# NRF24-zero-SHIM.net
KiCad netlist of a schematic drawn in EAGLE
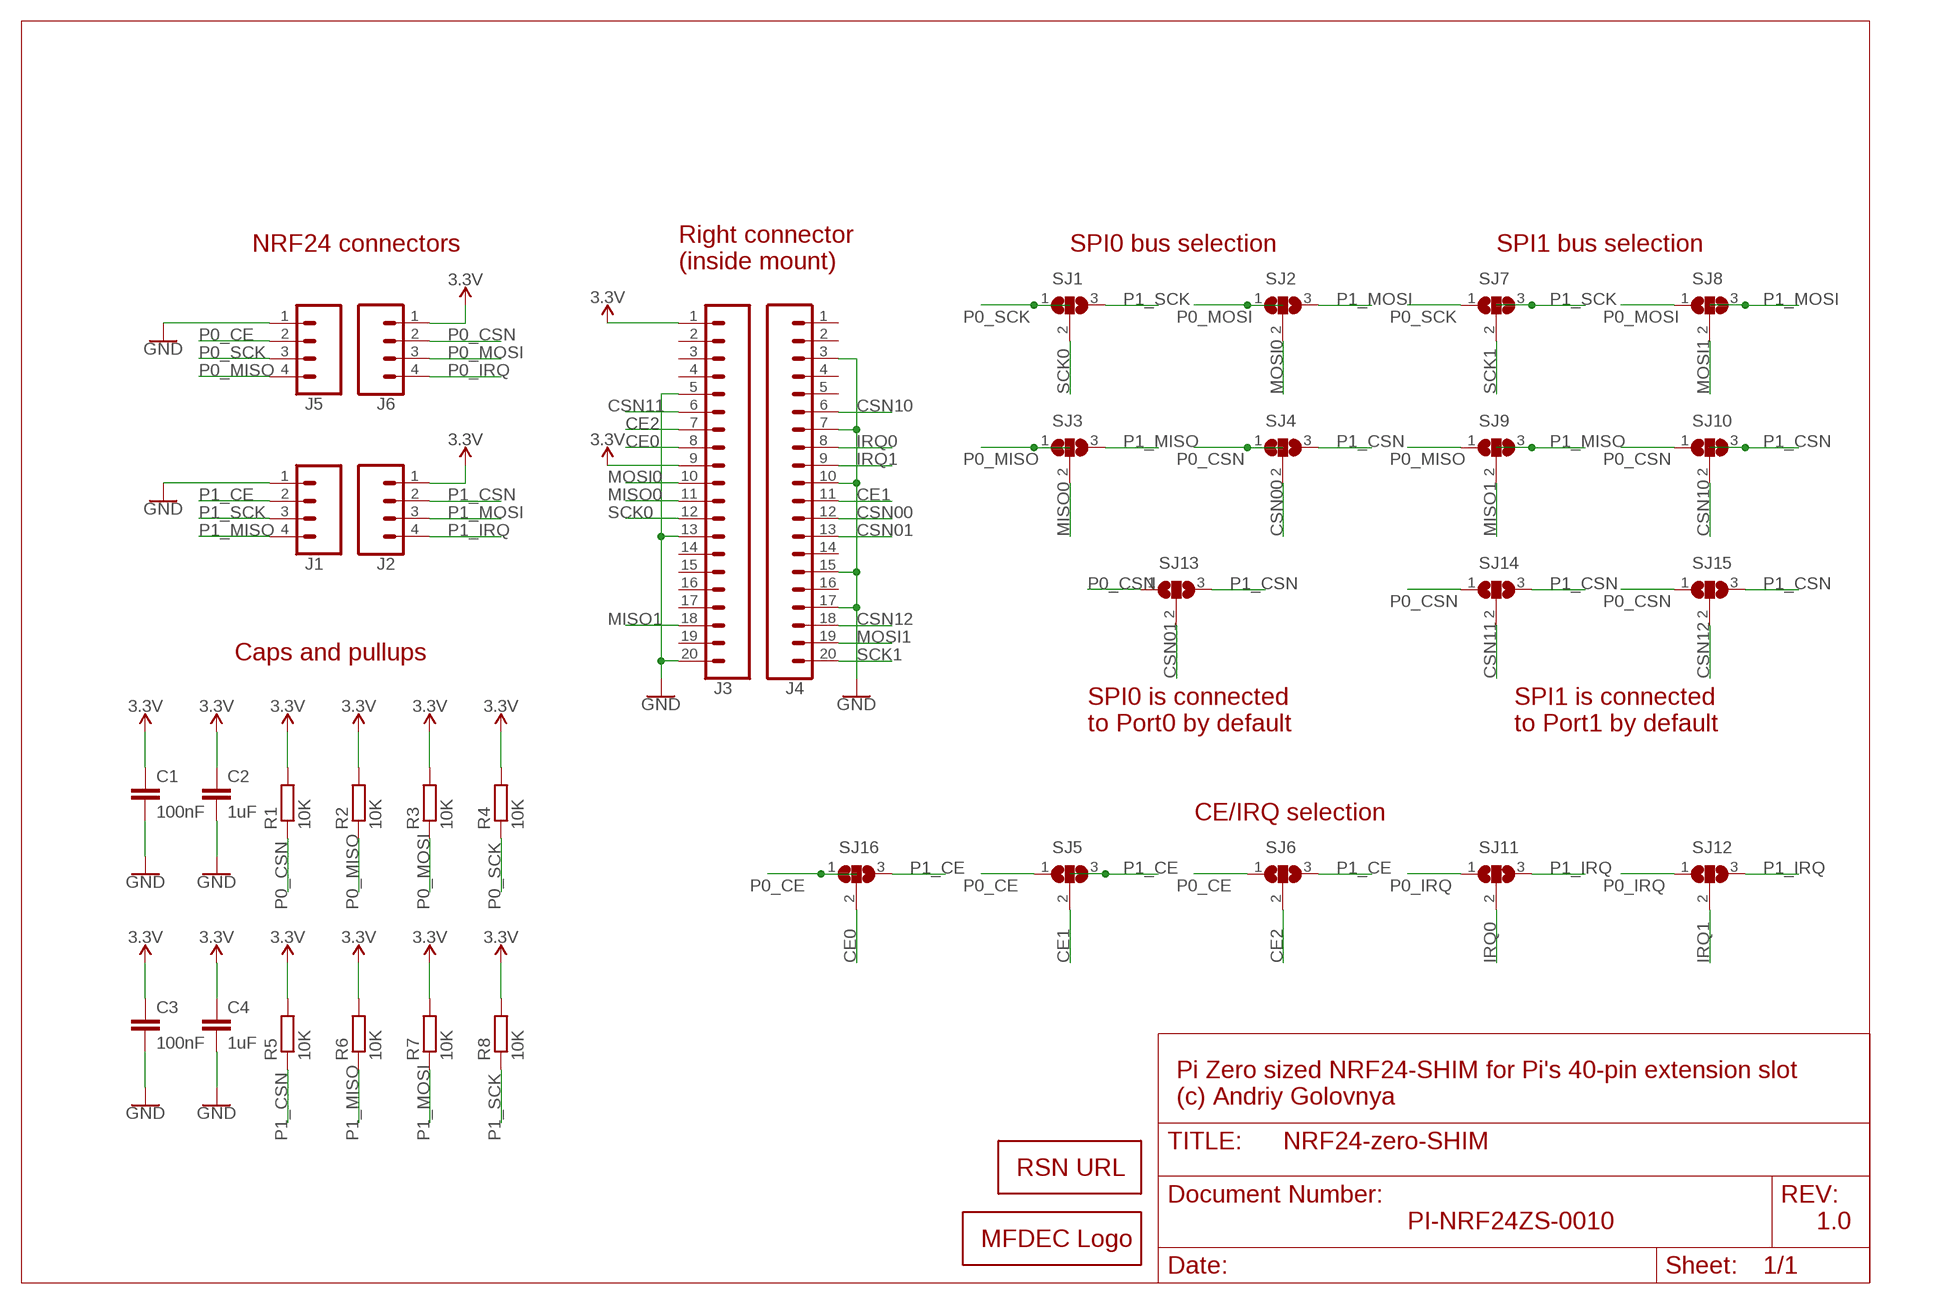
[diagram p0: schematic, sheet 1]

(export (version "E")
  (design (tool "Eeschema 10.0.6"))
  (components
    (comp (ref "C1")
      (value "100nF")
      (footprint "eagle-import:C0402")
      (libsource (lib "eagle-import") (part "C-EUC0402"))
    )
    (comp (ref "C2")
      (value "1uF")
      (footprint "eagle-import:C0603")
      (libsource (lib "eagle-import") (part "C-EUC0603"))
    )
    (comp (ref "C3")
      (value "100nF")
      (footprint "eagle-import:C0402")
      (libsource (lib "eagle-import") (part "C-EUC0402"))
    )
    (comp (ref "C4")
      (value "1uF")
      (footprint "eagle-import:C0603")
      (libsource (lib "eagle-import") (part "C-EUC0603"))
    )
    (comp (ref "J1")
      (value "CONN_04LOCK")
      (footprint "eagle-import:1X04_LOCK")
      (libsource (lib "eagle-import") (part "CONN_04LOCK"))
    )
    (comp (ref "J2")
      (value "CONN_04LOCK")
      (footprint "eagle-import:1X04_LOCK")
      (libsource (lib "eagle-import") (part "CONN_04LOCK"))
    )
    (comp (ref "J3")
      (value "CONN_20LOCK")
      (footprint "eagle-import:1X20_LOCK")
      (libsource (lib "eagle-import") (part "CONN_20LOCK"))
    )
    (comp (ref "J4")
      (value "CONN_20LOCK")
      (footprint "eagle-import:1X20_LOCK")
      (libsource (lib "eagle-import") (part "CONN_20LOCK"))
    )
    (comp (ref "J5")
      (value "CONN_04LOCK")
      (footprint "eagle-import:1X04_LOCK")
      (libsource (lib "eagle-import") (part "CONN_04LOCK"))
    )
    (comp (ref "J6")
      (value "CONN_04LOCK")
      (footprint "eagle-import:1X04_LOCK")
      (libsource (lib "eagle-import") (part "CONN_04LOCK"))
    )
    (comp (ref "LOGO1")
      (value "MFDECLOGO_SQ_8MM")
      (footprint "eagle-import:MFDEC_SQ_8MM")
      (libsource (lib "eagle-import") (part "MFDECLOGO_SQ_8MM"))
    )
    (comp (ref "LOGO3")
      (value "RSNURL_QR_10MM")
      (footprint "eagle-import:RSNURL_QR_10MM")
      (libsource (lib "eagle-import") (part "RSNURL_QR_10MM"))
    )
    (comp (ref "R1")
      (value "10K")
      (footprint "eagle-import:R0402")
      (libsource (lib "eagle-import") (part "R-EU_R0402"))
    )
    (comp (ref "R2")
      (value "10K")
      (footprint "eagle-import:R0402")
      (libsource (lib "eagle-import") (part "R-EU_R0402"))
    )
    (comp (ref "R3")
      (value "10K")
      (footprint "eagle-import:R0402")
      (libsource (lib "eagle-import") (part "R-EU_R0402"))
    )
    (comp (ref "R4")
      (value "10K")
      (footprint "eagle-import:R0402")
      (libsource (lib "eagle-import") (part "R-EU_R0402"))
    )
    (comp (ref "R5")
      (value "10K")
      (footprint "eagle-import:R0402")
      (libsource (lib "eagle-import") (part "R-EU_R0402"))
    )
    (comp (ref "R6")
      (value "10K")
      (footprint "eagle-import:R0402")
      (libsource (lib "eagle-import") (part "R-EU_R0402"))
    )
    (comp (ref "R7")
      (value "10K")
      (footprint "eagle-import:R0402")
      (libsource (lib "eagle-import") (part "R-EU_R0402"))
    )
    (comp (ref "R8")
      (value "10K")
      (footprint "eagle-import:R0402")
      (libsource (lib "eagle-import") (part "R-EU_R0402"))
    )
    (comp (ref "SJ1")
      (value "SJ2")
      (footprint "eagle-import:SJ_2")
      (libsource (lib "eagle-import") (part "SJ2"))
    )
    (comp (ref "SJ2")
      (value "SJ2")
      (footprint "eagle-import:SJ_2")
      (libsource (lib "eagle-import") (part "SJ2"))
    )
    (comp (ref "SJ3")
      (value "SJ2")
      (footprint "eagle-import:SJ_2")
      (libsource (lib "eagle-import") (part "SJ2"))
    )
    (comp (ref "SJ4")
      (value "SJ2")
      (footprint "eagle-import:SJ_2")
      (libsource (lib "eagle-import") (part "SJ2"))
    )
    (comp (ref "SJ5")
      (value "SJ2")
      (footprint "eagle-import:SJ_2")
      (libsource (lib "eagle-import") (part "SJ2"))
    )
    (comp (ref "SJ6")
      (value "SJ2")
      (footprint "eagle-import:SJ_2")
      (libsource (lib "eagle-import") (part "SJ2"))
    )
    (comp (ref "SJ7")
      (value "SJ2")
      (footprint "eagle-import:SJ_2")
      (libsource (lib "eagle-import") (part "SJ2"))
    )
    (comp (ref "SJ8")
      (value "SJ2")
      (footprint "eagle-import:SJ_2")
      (libsource (lib "eagle-import") (part "SJ2"))
    )
    (comp (ref "SJ9")
      (value "SJ2")
      (footprint "eagle-import:SJ_2")
      (libsource (lib "eagle-import") (part "SJ2"))
    )
    (comp (ref "SJ10")
      (value "SJ2")
      (footprint "eagle-import:SJ_2")
      (libsource (lib "eagle-import") (part "SJ2"))
    )
    (comp (ref "SJ11")
      (value "SJ2")
      (footprint "eagle-import:SJ_2")
      (libsource (lib "eagle-import") (part "SJ2"))
    )
    (comp (ref "SJ12")
      (value "SJ2")
      (footprint "eagle-import:SJ_2")
      (libsource (lib "eagle-import") (part "SJ2"))
    )
    (comp (ref "SJ13")
      (value "SJ2")
      (footprint "eagle-import:SJ_2")
      (libsource (lib "eagle-import") (part "SJ2"))
    )
    (comp (ref "SJ14")
      (value "SJ2")
      (footprint "eagle-import:SJ_2")
      (libsource (lib "eagle-import") (part "SJ2"))
    )
    (comp (ref "SJ15")
      (value "SJ2")
      (footprint "eagle-import:SJ_2")
      (libsource (lib "eagle-import") (part "SJ2"))
    )
    (comp (ref "SJ16")
      (value "SJ2")
      (footprint "eagle-import:SJ_2")
      (libsource (lib "eagle-import") (part "SJ2"))
    )
  )
  (nets
    (net (code "1") (name "/CE0") (class "Default")
      (node (ref "J3") (pin "8") (pinfunction "8_8") (pintype "passive"))
      (node (ref "SJ16") (pin "2") (pinfunction "2_2") (pintype "passive"))
    )
    (net (code "2") (name "/CE1") (class "Default")
      (node (ref "J4") (pin "11") (pinfunction "11_11") (pintype "passive"))
      (node (ref "SJ5") (pin "2") (pinfunction "2_2") (pintype "passive"))
    )
    (net (code "3") (name "/CE2") (class "Default")
      (node (ref "J3") (pin "7") (pinfunction "7_7") (pintype "passive"))
      (node (ref "SJ6") (pin "2") (pinfunction "2_2") (pintype "passive"))
    )
    (net (code "4") (name "/CSN00") (class "Default")
      (node (ref "J4") (pin "12") (pinfunction "12_12") (pintype "passive"))
      (node (ref "SJ4") (pin "2") (pinfunction "2_2") (pintype "passive"))
    )
    (net (code "5") (name "/CSN01") (class "Default")
      (node (ref "J4") (pin "13") (pinfunction "13_13") (pintype "passive"))
      (node (ref "SJ13") (pin "2") (pinfunction "2_2") (pintype "passive"))
    )
    (net (code "6") (name "/CSN10") (class "Default")
      (node (ref "J4") (pin "6") (pinfunction "6_6") (pintype "passive"))
      (node (ref "SJ10") (pin "2") (pinfunction "2_2") (pintype "passive"))
    )
    (net (code "7") (name "/CSN11") (class "Default")
      (node (ref "J3") (pin "6") (pinfunction "6_6") (pintype "passive"))
      (node (ref "SJ14") (pin "2") (pinfunction "2_2") (pintype "passive"))
    )
    (net (code "8") (name "/CSN12") (class "Default")
      (node (ref "J4") (pin "18") (pinfunction "18_18") (pintype "passive"))
      (node (ref "SJ15") (pin "2") (pinfunction "2_2") (pintype "passive"))
    )
    (net (code "9") (name "/IRQ0") (class "Default")
      (node (ref "J4") (pin "8") (pinfunction "8_8") (pintype "passive"))
      (node (ref "SJ11") (pin "2") (pinfunction "2_2") (pintype "passive"))
    )
    (net (code "10") (name "/IRQ1") (class "Default")
      (node (ref "J4") (pin "9") (pinfunction "9_9") (pintype "passive"))
      (node (ref "SJ12") (pin "2") (pinfunction "2_2") (pintype "passive"))
    )
    (net (code "11") (name "/MISO0") (class "Default")
      (node (ref "J3") (pin "11") (pinfunction "11_11") (pintype "passive"))
      (node (ref "SJ3") (pin "2") (pinfunction "2_2") (pintype "passive"))
    )
    (net (code "12") (name "/MISO1") (class "Default")
      (node (ref "J3") (pin "18") (pinfunction "18_18") (pintype "passive"))
      (node (ref "SJ9") (pin "2") (pinfunction "2_2") (pintype "passive"))
    )
    (net (code "13") (name "/MOSI0") (class "Default")
      (node (ref "J3") (pin "10") (pinfunction "10_10") (pintype "passive"))
      (node (ref "SJ2") (pin "2") (pinfunction "2_2") (pintype "passive"))
    )
    (net (code "14") (name "/MOSI1") (class "Default")
      (node (ref "J4") (pin "19") (pinfunction "19_19") (pintype "passive"))
      (node (ref "SJ8") (pin "2") (pinfunction "2_2") (pintype "passive"))
    )
    (net (code "15") (name "/P0_CE") (class "Default")
      (node (ref "J5") (pin "2") (pinfunction "2_2") (pintype "passive"))
      (node (ref "SJ16") (pin "1") (pinfunction "1_1") (pintype "passive"))
      (node (ref "SJ5") (pin "1") (pinfunction "1_1") (pintype "passive"))
      (node (ref "SJ6") (pin "1") (pinfunction "1_1") (pintype "passive"))
    )
    (net (code "16") (name "/P0_CSN") (class "Default")
      (node (ref "J6") (pin "2") (pinfunction "2_2") (pintype "passive"))
      (node (ref "R1") (pin "1") (pinfunction "1_1") (pintype "passive"))
      (node (ref "SJ10") (pin "1") (pinfunction "1_1") (pintype "passive"))
      (node (ref "SJ13") (pin "1") (pinfunction "1_1") (pintype "passive"))
      (node (ref "SJ14") (pin "1") (pinfunction "1_1") (pintype "passive"))
      (node (ref "SJ15") (pin "1") (pinfunction "1_1") (pintype "passive"))
      (node (ref "SJ4") (pin "1") (pinfunction "1_1") (pintype "passive"))
    )
    (net (code "17") (name "/P0_IRQ") (class "Default")
      (node (ref "J6") (pin "4") (pinfunction "4_4") (pintype "passive"))
      (node (ref "SJ11") (pin "1") (pinfunction "1_1") (pintype "passive"))
      (node (ref "SJ12") (pin "1") (pinfunction "1_1") (pintype "passive"))
    )
    (net (code "18") (name "/P0_MISO") (class "Default")
      (node (ref "J5") (pin "4") (pinfunction "4_4") (pintype "passive"))
      (node (ref "R2") (pin "1") (pinfunction "1_1") (pintype "passive"))
      (node (ref "SJ3") (pin "1") (pinfunction "1_1") (pintype "passive"))
      (node (ref "SJ9") (pin "1") (pinfunction "1_1") (pintype "passive"))
    )
    (net (code "19") (name "/P0_MOSI") (class "Default")
      (node (ref "J6") (pin "3") (pinfunction "3_3") (pintype "passive"))
      (node (ref "R3") (pin "1") (pinfunction "1_1") (pintype "passive"))
      (node (ref "SJ2") (pin "1") (pinfunction "1_1") (pintype "passive"))
      (node (ref "SJ8") (pin "1") (pinfunction "1_1") (pintype "passive"))
    )
    (net (code "20") (name "/P0_SCK") (class "Default")
      (node (ref "J5") (pin "3") (pinfunction "3_3") (pintype "passive"))
      (node (ref "R4") (pin "1") (pinfunction "1_1") (pintype "passive"))
      (node (ref "SJ1") (pin "1") (pinfunction "1_1") (pintype "passive"))
      (node (ref "SJ7") (pin "1") (pinfunction "1_1") (pintype "passive"))
    )
    (net (code "21") (name "/P1_CE") (class "Default")
      (node (ref "J1") (pin "2") (pinfunction "2_2") (pintype "passive"))
      (node (ref "SJ16") (pin "3") (pinfunction "3_3") (pintype "passive"))
      (node (ref "SJ5") (pin "3") (pinfunction "3_3") (pintype "passive"))
      (node (ref "SJ6") (pin "3") (pinfunction "3_3") (pintype "passive"))
    )
    (net (code "22") (name "/P1_CSN") (class "Default")
      (node (ref "J2") (pin "2") (pinfunction "2_2") (pintype "passive"))
      (node (ref "R5") (pin "1") (pinfunction "1_1") (pintype "passive"))
      (node (ref "SJ10") (pin "3") (pinfunction "3_3") (pintype "passive"))
      (node (ref "SJ13") (pin "3") (pinfunction "3_3") (pintype "passive"))
      (node (ref "SJ14") (pin "3") (pinfunction "3_3") (pintype "passive"))
      (node (ref "SJ15") (pin "3") (pinfunction "3_3") (pintype "passive"))
      (node (ref "SJ4") (pin "3") (pinfunction "3_3") (pintype "passive"))
    )
    (net (code "23") (name "/P1_IRQ") (class "Default")
      (node (ref "J2") (pin "4") (pinfunction "4_4") (pintype "passive"))
      (node (ref "SJ11") (pin "3") (pinfunction "3_3") (pintype "passive"))
      (node (ref "SJ12") (pin "3") (pinfunction "3_3") (pintype "passive"))
    )
    (net (code "24") (name "/P1_MISO") (class "Default")
      (node (ref "J1") (pin "4") (pinfunction "4_4") (pintype "passive"))
      (node (ref "R6") (pin "1") (pinfunction "1_1") (pintype "passive"))
      (node (ref "SJ3") (pin "3") (pinfunction "3_3") (pintype "passive"))
      (node (ref "SJ9") (pin "3") (pinfunction "3_3") (pintype "passive"))
    )
    (net (code "25") (name "/P1_MOSI") (class "Default")
      (node (ref "J2") (pin "3") (pinfunction "3_3") (pintype "passive"))
      (node (ref "R7") (pin "1") (pinfunction "1_1") (pintype "passive"))
      (node (ref "SJ2") (pin "3") (pinfunction "3_3") (pintype "passive"))
      (node (ref "SJ8") (pin "3") (pinfunction "3_3") (pintype "passive"))
    )
    (net (code "26") (name "/P1_SCK") (class "Default")
      (node (ref "J1") (pin "3") (pinfunction "3_3") (pintype "passive"))
      (node (ref "R8") (pin "1") (pinfunction "1_1") (pintype "passive"))
      (node (ref "SJ1") (pin "3") (pinfunction "3_3") (pintype "passive"))
      (node (ref "SJ7") (pin "3") (pinfunction "3_3") (pintype "passive"))
    )
    (net (code "27") (name "/SCK0") (class "Default")
      (node (ref "J3") (pin "12") (pinfunction "12_12") (pintype "passive"))
      (node (ref "SJ1") (pin "2") (pinfunction "2_2") (pintype "passive"))
    )
    (net (code "28") (name "/SCK1") (class "Default")
      (node (ref "J4") (pin "20") (pinfunction "20_20") (pintype "passive"))
      (node (ref "SJ7") (pin "2") (pinfunction "2_2") (pintype "passive"))
    )
    (net (code "29") (name "3.3V") (class "Default")
      (node (ref "C1") (pin "1") (pinfunction "1_1") (pintype "passive"))
      (node (ref "C2") (pin "1") (pinfunction "1_1") (pintype "passive"))
      (node (ref "C3") (pin "1") (pinfunction "1_1") (pintype "passive"))
      (node (ref "C4") (pin "1") (pinfunction "1_1") (pintype "passive"))
      (node (ref "J2") (pin "1") (pinfunction "1_1") (pintype "passive"))
      (node (ref "J3") (pin "1") (pinfunction "1_1") (pintype "passive"))
      (node (ref "J3") (pin "9") (pinfunction "9_9") (pintype "passive"))
      (node (ref "J6") (pin "1") (pinfunction "1_1") (pintype "passive"))
      (node (ref "R1") (pin "2") (pinfunction "2_2") (pintype "passive"))
      (node (ref "R2") (pin "2") (pinfunction "2_2") (pintype "passive"))
      (node (ref "R3") (pin "2") (pinfunction "2_2") (pintype "passive"))
      (node (ref "R4") (pin "2") (pinfunction "2_2") (pintype "passive"))
      (node (ref "R5") (pin "2") (pinfunction "2_2") (pintype "passive"))
      (node (ref "R6") (pin "2") (pinfunction "2_2") (pintype "passive"))
      (node (ref "R7") (pin "2") (pinfunction "2_2") (pintype "passive"))
      (node (ref "R8") (pin "2") (pinfunction "2_2") (pintype "passive"))
    )
    (net (code "30") (name "GND") (class "Default")
      (node (ref "C1") (pin "2") (pinfunction "2_2") (pintype "passive"))
      (node (ref "C2") (pin "2") (pinfunction "2_2") (pintype "passive"))
      (node (ref "C3") (pin "2") (pinfunction "2_2") (pintype "passive"))
      (node (ref "C4") (pin "2") (pinfunction "2_2") (pintype "passive"))
      (node (ref "J1") (pin "1") (pinfunction "1_1") (pintype "passive"))
      (node (ref "J3") (pin "13") (pinfunction "13_13") (pintype "passive"))
      (node (ref "J3") (pin "20") (pinfunction "20_20") (pintype "passive"))
      (node (ref "J3") (pin "5") (pinfunction "5_5") (pintype "passive"))
      (node (ref "J4") (pin "10") (pinfunction "10_10") (pintype "passive"))
      (node (ref "J4") (pin "15") (pinfunction "15_15") (pintype "passive"))
      (node (ref "J4") (pin "17") (pinfunction "17_17") (pintype "passive"))
      (node (ref "J4") (pin "3") (pinfunction "3_3") (pintype "passive"))
      (node (ref "J4") (pin "7") (pinfunction "7_7") (pintype "passive"))
      (node (ref "J5") (pin "1") (pinfunction "1_1") (pintype "passive"))
    )
    (net (code "31") (name "unconnected-(J3-Pad2)") (class "Default")
      (node (ref "J3") (pin "2") (pinfunction "2_2") (pintype "passive"))
    )
    (net (code "32") (name "unconnected-(J3-Pad3)") (class "Default")
      (node (ref "J3") (pin "3") (pinfunction "3_3") (pintype "passive"))
    )
    (net (code "33") (name "unconnected-(J3-Pad4)") (class "Default")
      (node (ref "J3") (pin "4") (pinfunction "4_4") (pintype "passive"))
    )
    (net (code "34") (name "unconnected-(J3-Pad14)") (class "Default")
      (node (ref "J3") (pin "14") (pinfunction "14_14") (pintype "passive"))
    )
    (net (code "35") (name "unconnected-(J3-Pad15)") (class "Default")
      (node (ref "J3") (pin "15") (pinfunction "15_15") (pintype "passive"))
    )
    (net (code "36") (name "unconnected-(J3-Pad16)") (class "Default")
      (node (ref "J3") (pin "16") (pinfunction "16_16") (pintype "passive"))
    )
    (net (code "37") (name "unconnected-(J3-Pad17)") (class "Default")
      (node (ref "J3") (pin "17") (pinfunction "17_17") (pintype "passive"))
    )
    (net (code "38") (name "unconnected-(J3-Pad19)") (class "Default")
      (node (ref "J3") (pin "19") (pinfunction "19_19") (pintype "passive"))
    )
    (net (code "39") (name "unconnected-(J4-Pad1)") (class "Default")
      (node (ref "J4") (pin "1") (pinfunction "1_1") (pintype "passive"))
    )
    (net (code "40") (name "unconnected-(J4-Pad2)") (class "Default")
      (node (ref "J4") (pin "2") (pinfunction "2_2") (pintype "passive"))
    )
    (net (code "41") (name "unconnected-(J4-Pad4)") (class "Default")
      (node (ref "J4") (pin "4") (pinfunction "4_4") (pintype "passive"))
    )
    (net (code "42") (name "unconnected-(J4-Pad5)") (class "Default")
      (node (ref "J4") (pin "5") (pinfunction "5_5") (pintype "passive"))
    )
    (net (code "43") (name "unconnected-(J4-Pad14)") (class "Default")
      (node (ref "J4") (pin "14") (pinfunction "14_14") (pintype "passive"))
    )
    (net (code "44") (name "unconnected-(J4-Pad16)") (class "Default")
      (node (ref "J4") (pin "16") (pinfunction "16_16") (pintype "passive"))
    )
  )
)
